# Arduino_Mega_SRAM_Tester.net
KiCad netlist of a schematic drawn in EAGLE
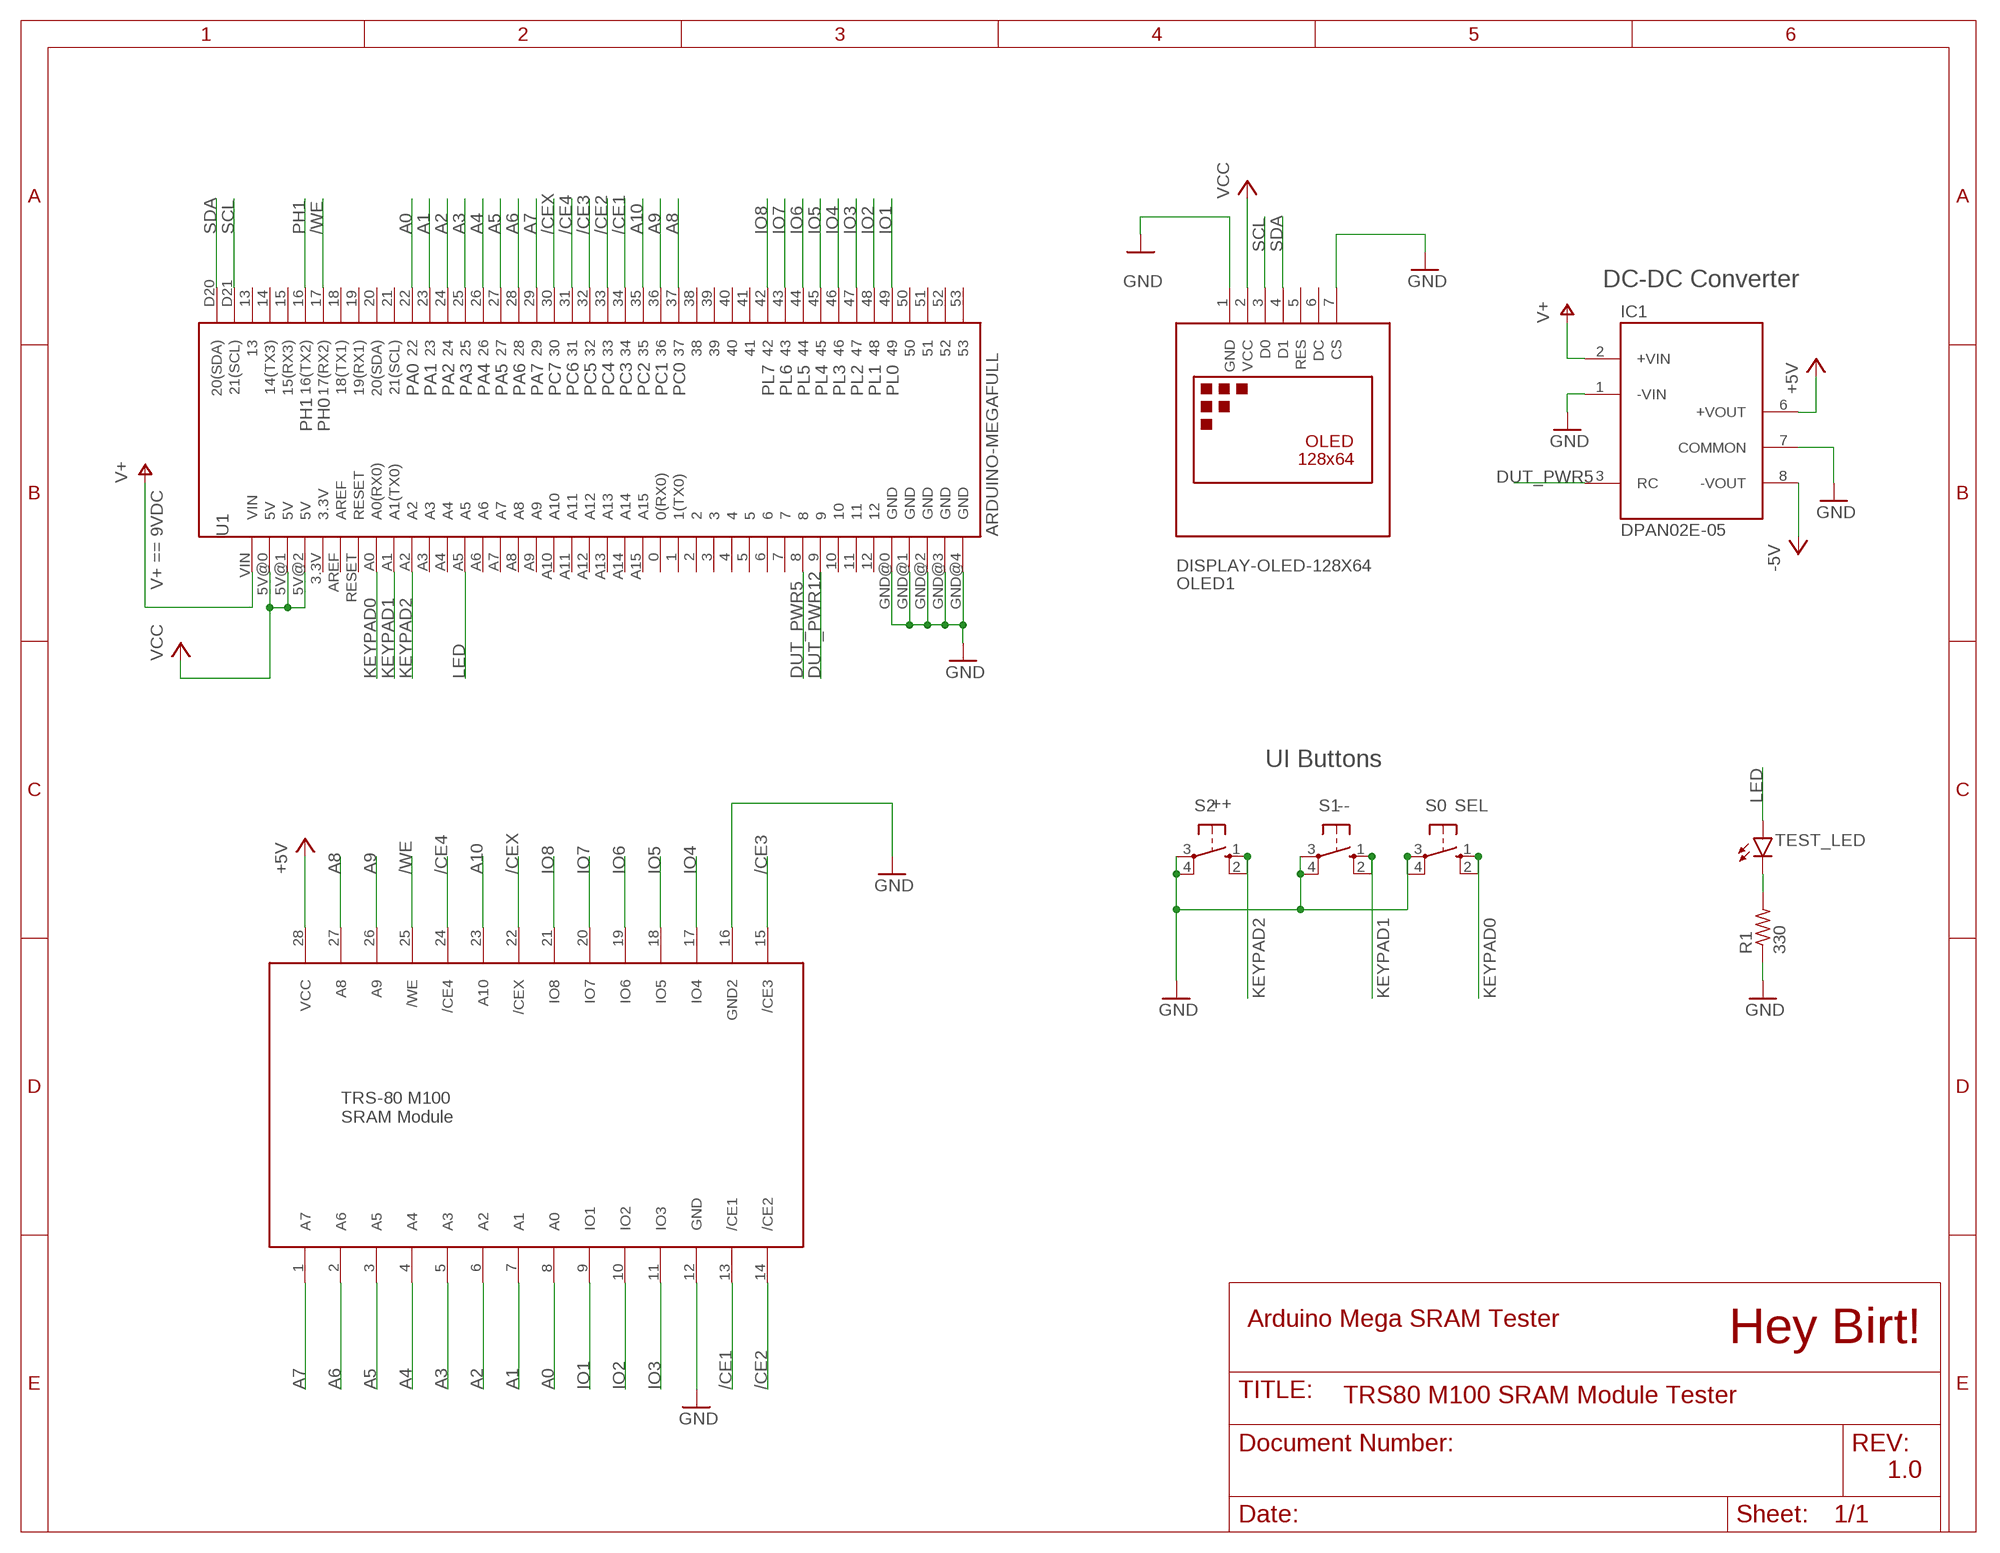
[diagram p0: schematic, sheet 1]

(export (version "E")
  (design (tool "Eeschema 10.0.6"))
  (components
    (comp (ref "IC1")
      (value "DPAN02E-05")
      (footprint "eagle-import:SIP7")
      (libsource (lib "eagle-import") (part "DPAN02"))
    )
    (comp (ref "LED1")
      (value "TEST_LED")
      (footprint "eagle-import:LED3MM")
      (libsource (lib "eagle-import") (part "LED3MM"))
    )
    (comp (ref "OLED1")
      (value "DISPLAY-OLED-128X64")
      (footprint "eagle-import:DISPLAY-OLED-128X64")
      (libsource (lib "eagle-import") (part "DISPLAY-OLED-128X64"))
    )
    (comp (ref "R1")
      (value "330")
      (footprint "eagle-import:0411_15")
      (libsource (lib "eagle-import") (part "R-US_0411/15"))
    )
    (comp (ref "S0")
      (value "SEL")
      (footprint "eagle-import:B3F-10XX")
      (fields (field (name "MPN") "B3F-1000"))
      (libsource (lib "eagle-import") (part "10-XX"))
    )
    (comp (ref "S1")
      (value "--")
      (footprint "eagle-import:B3F-10XX")
      (fields (field (name "MPN") "B3F-1000"))
      (libsource (lib "eagle-import") (part "10-XX"))
    )
    (comp (ref "S2")
      (value "++")
      (footprint "eagle-import:B3F-10XX")
      (fields (field (name "MPN") "B3F-1000"))
      (libsource (lib "eagle-import") (part "10-XX"))
    )
    (comp (ref "U$2")
      (value "M100_SRAMDIL0.7")
      (footprint "eagle-import:DIL28-6")
      (libsource (lib "eagle-import") (part "M100_SRAMDIL0.7"))
    )
    (comp (ref "U1")
      (value "ARDUINO-MEGAFULL")
      (footprint "eagle-import:ARDUINO_MEGA")
      (libsource (lib "eagle-import") (part "ARDUINO-MEGAFULL"))
    )
  )
  (nets
    (net (code "1") (name "+5V") (class "Default")
      (node (ref "IC1") (pin "6") (pinfunction "+VOUT_6") (pintype "passive"))
      (node (ref "U$2") (pin "28") (pinfunction "VCC_28") (pintype "power_in"))
    )
    (net (code "2") (name "-5V") (class "Default")
      (node (ref "IC1") (pin "8") (pinfunction "-VOUT_8") (pintype "passive"))
    )
    (net (code "3") (name "/A0") (class "Default")
      (node (ref "U$2") (pin "8") (pinfunction "A0_8") (pintype "bidirectional"))
      (node (ref "U1") (pin "22") (pinfunction "22_22") (pintype "bidirectional"))
    )
    (net (code "4") (name "/A1") (class "Default")
      (node (ref "U$2") (pin "7") (pinfunction "A1_7") (pintype "bidirectional"))
      (node (ref "U1") (pin "23") (pinfunction "23_23") (pintype "bidirectional"))
    )
    (net (code "5") (name "/A2") (class "Default")
      (node (ref "U$2") (pin "6") (pinfunction "A2_6") (pintype "bidirectional"))
      (node (ref "U1") (pin "24") (pinfunction "24_24") (pintype "bidirectional"))
    )
    (net (code "6") (name "/A3") (class "Default")
      (node (ref "U$2") (pin "5") (pinfunction "A3_5") (pintype "bidirectional"))
      (node (ref "U1") (pin "25") (pinfunction "25_25") (pintype "bidirectional"))
    )
    (net (code "7") (name "/A4") (class "Default")
      (node (ref "U$2") (pin "4") (pinfunction "A4_4") (pintype "bidirectional"))
      (node (ref "U1") (pin "26") (pinfunction "26_26") (pintype "bidirectional"))
    )
    (net (code "8") (name "/A5") (class "Default")
      (node (ref "U$2") (pin "3") (pinfunction "A5_3") (pintype "bidirectional"))
      (node (ref "U1") (pin "27") (pinfunction "27_27") (pintype "bidirectional"))
    )
    (net (code "9") (name "/A6") (class "Default")
      (node (ref "U$2") (pin "2") (pinfunction "A6_2") (pintype "bidirectional"))
      (node (ref "U1") (pin "28") (pinfunction "28_28") (pintype "bidirectional"))
    )
    (net (code "10") (name "/A7") (class "Default")
      (node (ref "U$2") (pin "1") (pinfunction "A7_1") (pintype "bidirectional"))
      (node (ref "U1") (pin "29") (pinfunction "29_29") (pintype "bidirectional"))
    )
    (net (code "11") (name "/A8") (class "Default")
      (node (ref "U$2") (pin "27") (pinfunction "A8_27") (pintype "bidirectional"))
      (node (ref "U1") (pin "37") (pinfunction "37_37") (pintype "bidirectional"))
    )
    (net (code "12") (name "/A9") (class "Default")
      (node (ref "U$2") (pin "26") (pinfunction "A9_26") (pintype "bidirectional"))
      (node (ref "U1") (pin "36") (pinfunction "36_36") (pintype "bidirectional"))
    )
    (net (code "13") (name "/A10") (class "Default")
      (node (ref "U$2") (pin "23") (pinfunction "A10_23") (pintype "bidirectional"))
      (node (ref "U1") (pin "35") (pinfunction "35_35") (pintype "bidirectional"))
    )
    (net (code "14") (name "/DUT_PWR5") (class "Default")
      (node (ref "IC1") (pin "3") (pinfunction "RC_3") (pintype "input"))
      (node (ref "U1") (pin "8") (pinfunction "8_8") (pintype "bidirectional"))
    )
    (net (code "15") (name "/DUT_PWR12") (class "Default")
      (node (ref "U1") (pin "9") (pinfunction "9_9") (pintype "bidirectional"))
    )
    (net (code "16") (name "/IO1") (class "Default")
      (node (ref "U$2") (pin "9") (pinfunction "IO1_9") (pintype "bidirectional"))
      (node (ref "U1") (pin "49") (pinfunction "49_49") (pintype "bidirectional"))
    )
    (net (code "17") (name "/IO2") (class "Default")
      (node (ref "U$2") (pin "10") (pinfunction "IO2_10") (pintype "bidirectional"))
      (node (ref "U1") (pin "48") (pinfunction "48_48") (pintype "bidirectional"))
    )
    (net (code "18") (name "/IO3") (class "Default")
      (node (ref "U$2") (pin "11") (pinfunction "IO3_11") (pintype "bidirectional"))
      (node (ref "U1") (pin "47") (pinfunction "47_47") (pintype "bidirectional"))
    )
    (net (code "19") (name "/IO4") (class "Default")
      (node (ref "U$2") (pin "17") (pinfunction "IO4_17") (pintype "bidirectional"))
      (node (ref "U1") (pin "46") (pinfunction "46_46") (pintype "bidirectional"))
    )
    (net (code "20") (name "/IO5") (class "Default")
      (node (ref "U$2") (pin "18") (pinfunction "IO5_18") (pintype "bidirectional"))
      (node (ref "U1") (pin "45") (pinfunction "45_45") (pintype "bidirectional"))
    )
    (net (code "21") (name "/IO6") (class "Default")
      (node (ref "U$2") (pin "19") (pinfunction "IO6_19") (pintype "bidirectional"))
      (node (ref "U1") (pin "44") (pinfunction "44_44") (pintype "bidirectional"))
    )
    (net (code "22") (name "/IO7") (class "Default")
      (node (ref "U$2") (pin "20") (pinfunction "IO7_20") (pintype "bidirectional"))
      (node (ref "U1") (pin "43") (pinfunction "43_43") (pintype "bidirectional"))
    )
    (net (code "23") (name "/IO8") (class "Default")
      (node (ref "U$2") (pin "21") (pinfunction "IO8_21") (pintype "bidirectional"))
      (node (ref "U1") (pin "42") (pinfunction "42_42") (pintype "bidirectional"))
    )
    (net (code "24") (name "/KEYPAD0") (class "Default")
      (node (ref "S0") (pin "1") (pinfunction "S_1") (pintype "passive"))
      (node (ref "S0") (pin "2") (pinfunction "S1_2") (pintype "passive"))
      (node (ref "U1") (pin "A0") (pinfunction "A0(RX0)_A0") (pintype "bidirectional"))
    )
    (net (code "25") (name "/KEYPAD1") (class "Default")
      (node (ref "S1") (pin "1") (pinfunction "S_1") (pintype "passive"))
      (node (ref "S1") (pin "2") (pinfunction "S1_2") (pintype "passive"))
      (node (ref "U1") (pin "A1") (pinfunction "A1(TX0)_A1") (pintype "bidirectional"))
    )
    (net (code "26") (name "/KEYPAD2") (class "Default")
      (node (ref "S2") (pin "1") (pinfunction "S_1") (pintype "passive"))
      (node (ref "S2") (pin "2") (pinfunction "S1_2") (pintype "passive"))
      (node (ref "U1") (pin "A2") (pinfunction "A2_A2") (pintype "bidirectional"))
    )
    (net (code "27") (name "/LED") (class "Default")
      (node (ref "LED1") (pin "A") (pinfunction "A_A") (pintype "passive"))
      (node (ref "U1") (pin "A5") (pinfunction "A5_A5") (pintype "bidirectional"))
    )
    (net (code "28") (name "/PH1") (class "Default")
      (node (ref "U1") (pin "16") (pinfunction "16(TX2)_16") (pintype "bidirectional"))
    )
    (net (code "29") (name "/SCL") (class "Default")
      (node (ref "OLED1") (pin "3") (pinfunction "D0_3") (pintype "bidirectional"))
      (node (ref "U1") (pin "D21") (pinfunction "21(SCL)_D21") (pintype "bidirectional"))
    )
    (net (code "30") (name "/SDA") (class "Default")
      (node (ref "OLED1") (pin "4") (pinfunction "D1_4") (pintype "bidirectional"))
      (node (ref "U1") (pin "D20") (pinfunction "20(SDA)_D20") (pintype "bidirectional"))
    )
    (net (code "31") (name "/{slash}CE1") (class "Default")
      (node (ref "U$2") (pin "13") (pinfunction "/CE1_13") (pintype "input"))
      (node (ref "U1") (pin "34") (pinfunction "34_34") (pintype "bidirectional"))
    )
    (net (code "32") (name "/{slash}CE2") (class "Default")
      (node (ref "U$2") (pin "14") (pinfunction "/CE2_14") (pintype "input"))
      (node (ref "U1") (pin "33") (pinfunction "33_33") (pintype "bidirectional"))
    )
    (net (code "33") (name "/{slash}CE3") (class "Default")
      (node (ref "U$2") (pin "15") (pinfunction "/CE3_15") (pintype "input"))
      (node (ref "U1") (pin "32") (pinfunction "32_32") (pintype "bidirectional"))
    )
    (net (code "34") (name "/{slash}CE4") (class "Default")
      (node (ref "U$2") (pin "24") (pinfunction "/CE4_24") (pintype "bidirectional"))
      (node (ref "U1") (pin "31") (pinfunction "31_31") (pintype "bidirectional"))
    )
    (net (code "35") (name "/{slash}CEX") (class "Default")
      (node (ref "U$2") (pin "22") (pinfunction "/CEX_22") (pintype "input"))
      (node (ref "U1") (pin "30") (pinfunction "30_30") (pintype "bidirectional"))
    )
    (net (code "36") (name "/{slash}WE") (class "Default")
      (node (ref "U$2") (pin "25") (pinfunction "/WE_25") (pintype "bidirectional"))
      (node (ref "U1") (pin "17") (pinfunction "17(RX2)_17") (pintype "bidirectional"))
    )
    (net (code "37") (name "GND") (class "Default")
      (node (ref "IC1") (pin "1") (pinfunction "-VIN_1") (pintype "input"))
      (node (ref "IC1") (pin "7") (pinfunction "COMMON_7") (pintype "passive"))
      (node (ref "OLED1") (pin "1") (pinfunction "GND_1") (pintype "power_in"))
      (node (ref "OLED1") (pin "7") (pinfunction "CS_7") (pintype "bidirectional"))
      (node (ref "R1") (pin "1") (pinfunction "1_1") (pintype "passive"))
      (node (ref "S0") (pin "3") (pinfunction "P_3") (pintype "passive"))
      (node (ref "S0") (pin "4") (pinfunction "P1_4") (pintype "passive"))
      (node (ref "S1") (pin "3") (pinfunction "P_3") (pintype "passive"))
      (node (ref "S1") (pin "4") (pinfunction "P1_4") (pintype "passive"))
      (node (ref "S2") (pin "3") (pinfunction "P_3") (pintype "passive"))
      (node (ref "S2") (pin "4") (pinfunction "P1_4") (pintype "passive"))
      (node (ref "U$2") (pin "12") (pinfunction "GND_12") (pintype "power_in"))
      (node (ref "U$2") (pin "16") (pinfunction "GND2_16") (pintype "power_in"))
      (node (ref "U1") (pin "GND@0") (pinfunction "GND_GND@0") (pintype "bidirectional"))
      (node (ref "U1") (pin "GND@1") (pinfunction "GND_GND@1") (pintype "bidirectional"))
      (node (ref "U1") (pin "GND@2") (pinfunction "GND_GND@2") (pintype "bidirectional"))
      (node (ref "U1") (pin "GND@3") (pinfunction "GND_GND@3") (pintype "bidirectional"))
      (node (ref "U1") (pin "GND@4") (pinfunction "GND_GND@4") (pintype "bidirectional"))
    )
    (net (code "38") (name "Net-(LED1-C)") (class "Default")
      (node (ref "LED1") (pin "K") (pinfunction "C_K") (pintype "passive"))
      (node (ref "R1") (pin "2") (pinfunction "2_2") (pintype "passive"))
    )
    (net (code "39") (name "V+") (class "Default")
      (node (ref "IC1") (pin "2") (pinfunction "+VIN_2") (pintype "input"))
      (node (ref "U1") (pin "VIN") (pinfunction "VIN_VIN") (pintype "bidirectional"))
    )
    (net (code "40") (name "VCC") (class "Default")
      (node (ref "OLED1") (pin "2") (pinfunction "VCC_2") (pintype "power_in"))
      (node (ref "U1") (pin "5V@0") (pinfunction "5V_5V@0") (pintype "bidirectional"))
      (node (ref "U1") (pin "5V@1") (pinfunction "5V_5V@1") (pintype "bidirectional"))
      (node (ref "U1") (pin "5V@2") (pinfunction "5V_5V@2") (pintype "bidirectional"))
    )
    (net (code "41") (name "unconnected-(OLED1-DC-Pad6)") (class "Default")
      (node (ref "OLED1") (pin "6") (pinfunction "DC_6") (pintype "bidirectional"))
    )
    (net (code "42") (name "unconnected-(OLED1-RES-Pad5)") (class "Default")
      (node (ref "OLED1") (pin "5") (pinfunction "RES_5") (pintype "bidirectional"))
    )
    (net (code "43") (name "unconnected-(U1-0(RX0)-Pad0)") (class "Default")
      (node (ref "U1") (pin "0") (pinfunction "0(RX0)_0") (pintype "bidirectional"))
    )
    (net (code "44") (name "unconnected-(U1-1(TX0)-Pad1)") (class "Default")
      (node (ref "U1") (pin "1") (pinfunction "1(TX0)_1") (pintype "bidirectional"))
    )
    (net (code "45") (name "unconnected-(U1-14(TX3)-Pad14)") (class "Default")
      (node (ref "U1") (pin "14") (pinfunction "14(TX3)_14") (pintype "bidirectional"))
    )
    (net (code "46") (name "unconnected-(U1-15(RX3)-Pad15)") (class "Default")
      (node (ref "U1") (pin "15") (pinfunction "15(RX3)_15") (pintype "bidirectional"))
    )
    (net (code "47") (name "unconnected-(U1-18(TX1)-Pad18)") (class "Default")
      (node (ref "U1") (pin "18") (pinfunction "18(TX1)_18") (pintype "bidirectional"))
    )
    (net (code "48") (name "unconnected-(U1-19(RX1)-Pad19)") (class "Default")
      (node (ref "U1") (pin "19") (pinfunction "19(RX1)_19") (pintype "bidirectional"))
    )
    (net (code "49") (name "unconnected-(U1-20(SDA)-Pad20)") (class "Default")
      (node (ref "U1") (pin "20") (pinfunction "20(SDA)_20") (pintype "bidirectional"))
    )
    (net (code "50") (name "unconnected-(U1-21(SCL)-Pad21)") (class "Default")
      (node (ref "U1") (pin "21") (pinfunction "21(SCL)_21") (pintype "bidirectional"))
    )
    (net (code "51") (name "unconnected-(U1-Pad2)") (class "Default")
      (node (ref "U1") (pin "2") (pinfunction "2_2") (pintype "bidirectional"))
    )
    (net (code "52") (name "unconnected-(U1-Pad3)") (class "Default")
      (node (ref "U1") (pin "3") (pinfunction "3_3") (pintype "bidirectional"))
    )
    (net (code "53") (name "unconnected-(U1-Pad3.3V)") (class "Default")
      (node (ref "U1") (pin "3.3V") (pinfunction "3.3V_3.3V") (pintype "bidirectional"))
    )
    (net (code "54") (name "unconnected-(U1-Pad4)") (class "Default")
      (node (ref "U1") (pin "4") (pinfunction "4_4") (pintype "bidirectional"))
    )
    (net (code "55") (name "unconnected-(U1-Pad5)") (class "Default")
      (node (ref "U1") (pin "5") (pinfunction "5_5") (pintype "bidirectional"))
    )
    (net (code "56") (name "unconnected-(U1-Pad6)") (class "Default")
      (node (ref "U1") (pin "6") (pinfunction "6_6") (pintype "bidirectional"))
    )
    (net (code "57") (name "unconnected-(U1-Pad7)") (class "Default")
      (node (ref "U1") (pin "7") (pinfunction "7_7") (pintype "bidirectional"))
    )
    (net (code "58") (name "unconnected-(U1-Pad10)") (class "Default")
      (node (ref "U1") (pin "10") (pinfunction "10_10") (pintype "bidirectional"))
    )
    (net (code "59") (name "unconnected-(U1-Pad11)") (class "Default")
      (node (ref "U1") (pin "11") (pinfunction "11_11") (pintype "bidirectional"))
    )
    (net (code "60") (name "unconnected-(U1-Pad12)") (class "Default")
      (node (ref "U1") (pin "12") (pinfunction "12_12") (pintype "bidirectional"))
    )
    (net (code "61") (name "unconnected-(U1-Pad13)") (class "Default")
      (node (ref "U1") (pin "13") (pinfunction "13_13") (pintype "bidirectional"))
    )
    (net (code "62") (name "unconnected-(U1-Pad38)") (class "Default")
      (node (ref "U1") (pin "38") (pinfunction "38_38") (pintype "bidirectional"))
    )
    (net (code "63") (name "unconnected-(U1-Pad39)") (class "Default")
      (node (ref "U1") (pin "39") (pinfunction "39_39") (pintype "bidirectional"))
    )
    (net (code "64") (name "unconnected-(U1-Pad40)") (class "Default")
      (node (ref "U1") (pin "40") (pinfunction "40_40") (pintype "bidirectional"))
    )
    (net (code "65") (name "unconnected-(U1-Pad41)") (class "Default")
      (node (ref "U1") (pin "41") (pinfunction "41_41") (pintype "bidirectional"))
    )
    (net (code "66") (name "unconnected-(U1-Pad50)") (class "Default")
      (node (ref "U1") (pin "50") (pinfunction "50_50") (pintype "bidirectional"))
    )
    (net (code "67") (name "unconnected-(U1-Pad51)") (class "Default")
      (node (ref "U1") (pin "51") (pinfunction "51_51") (pintype "bidirectional"))
    )
    (net (code "68") (name "unconnected-(U1-Pad52)") (class "Default")
      (node (ref "U1") (pin "52") (pinfunction "52_52") (pintype "bidirectional"))
    )
    (net (code "69") (name "unconnected-(U1-Pad53)") (class "Default")
      (node (ref "U1") (pin "53") (pinfunction "53_53") (pintype "bidirectional"))
    )
    (net (code "70") (name "unconnected-(U1-PadA3)") (class "Default")
      (node (ref "U1") (pin "A3") (pinfunction "A3_A3") (pintype "bidirectional"))
    )
    (net (code "71") (name "unconnected-(U1-PadA4)") (class "Default")
      (node (ref "U1") (pin "A4") (pinfunction "A4_A4") (pintype "bidirectional"))
    )
    (net (code "72") (name "unconnected-(U1-PadA6)") (class "Default")
      (node (ref "U1") (pin "A6") (pinfunction "A6_A6") (pintype "bidirectional"))
    )
    (net (code "73") (name "unconnected-(U1-PadA7)") (class "Default")
      (node (ref "U1") (pin "A7") (pinfunction "A7_A7") (pintype "bidirectional"))
    )
    (net (code "74") (name "unconnected-(U1-PadA8)") (class "Default")
      (node (ref "U1") (pin "A8") (pinfunction "A8_A8") (pintype "bidirectional"))
    )
    (net (code "75") (name "unconnected-(U1-PadA9)") (class "Default")
      (node (ref "U1") (pin "A9") (pinfunction "A9_A9") (pintype "bidirectional"))
    )
    (net (code "76") (name "unconnected-(U1-PadA10)") (class "Default")
      (node (ref "U1") (pin "A10") (pinfunction "A10_A10") (pintype "bidirectional"))
    )
    (net (code "77") (name "unconnected-(U1-PadA11)") (class "Default")
      (node (ref "U1") (pin "A11") (pinfunction "A11_A11") (pintype "bidirectional"))
    )
    (net (code "78") (name "unconnected-(U1-PadA12)") (class "Default")
      (node (ref "U1") (pin "A12") (pinfunction "A12_A12") (pintype "bidirectional"))
    )
    (net (code "79") (name "unconnected-(U1-PadA13)") (class "Default")
      (node (ref "U1") (pin "A13") (pinfunction "A13_A13") (pintype "bidirectional"))
    )
    (net (code "80") (name "unconnected-(U1-PadA14)") (class "Default")
      (node (ref "U1") (pin "A14") (pinfunction "A14_A14") (pintype "bidirectional"))
    )
    (net (code "81") (name "unconnected-(U1-PadA15)") (class "Default")
      (node (ref "U1") (pin "A15") (pinfunction "A15_A15") (pintype "bidirectional"))
    )
    (net (code "82") (name "unconnected-(U1-PadAREF)") (class "Default")
      (node (ref "U1") (pin "AREF") (pinfunction "AREF_AREF") (pintype "bidirectional"))
    )
    (net (code "83") (name "unconnected-(U1-PadRESET)") (class "Default")
      (node (ref "U1") (pin "RESET") (pinfunction "RESET_RESET") (pintype "bidirectional"))
    )
  )
)
